# curcut_design.net
KiCad netlist of a schematic drawn in EasyEDA
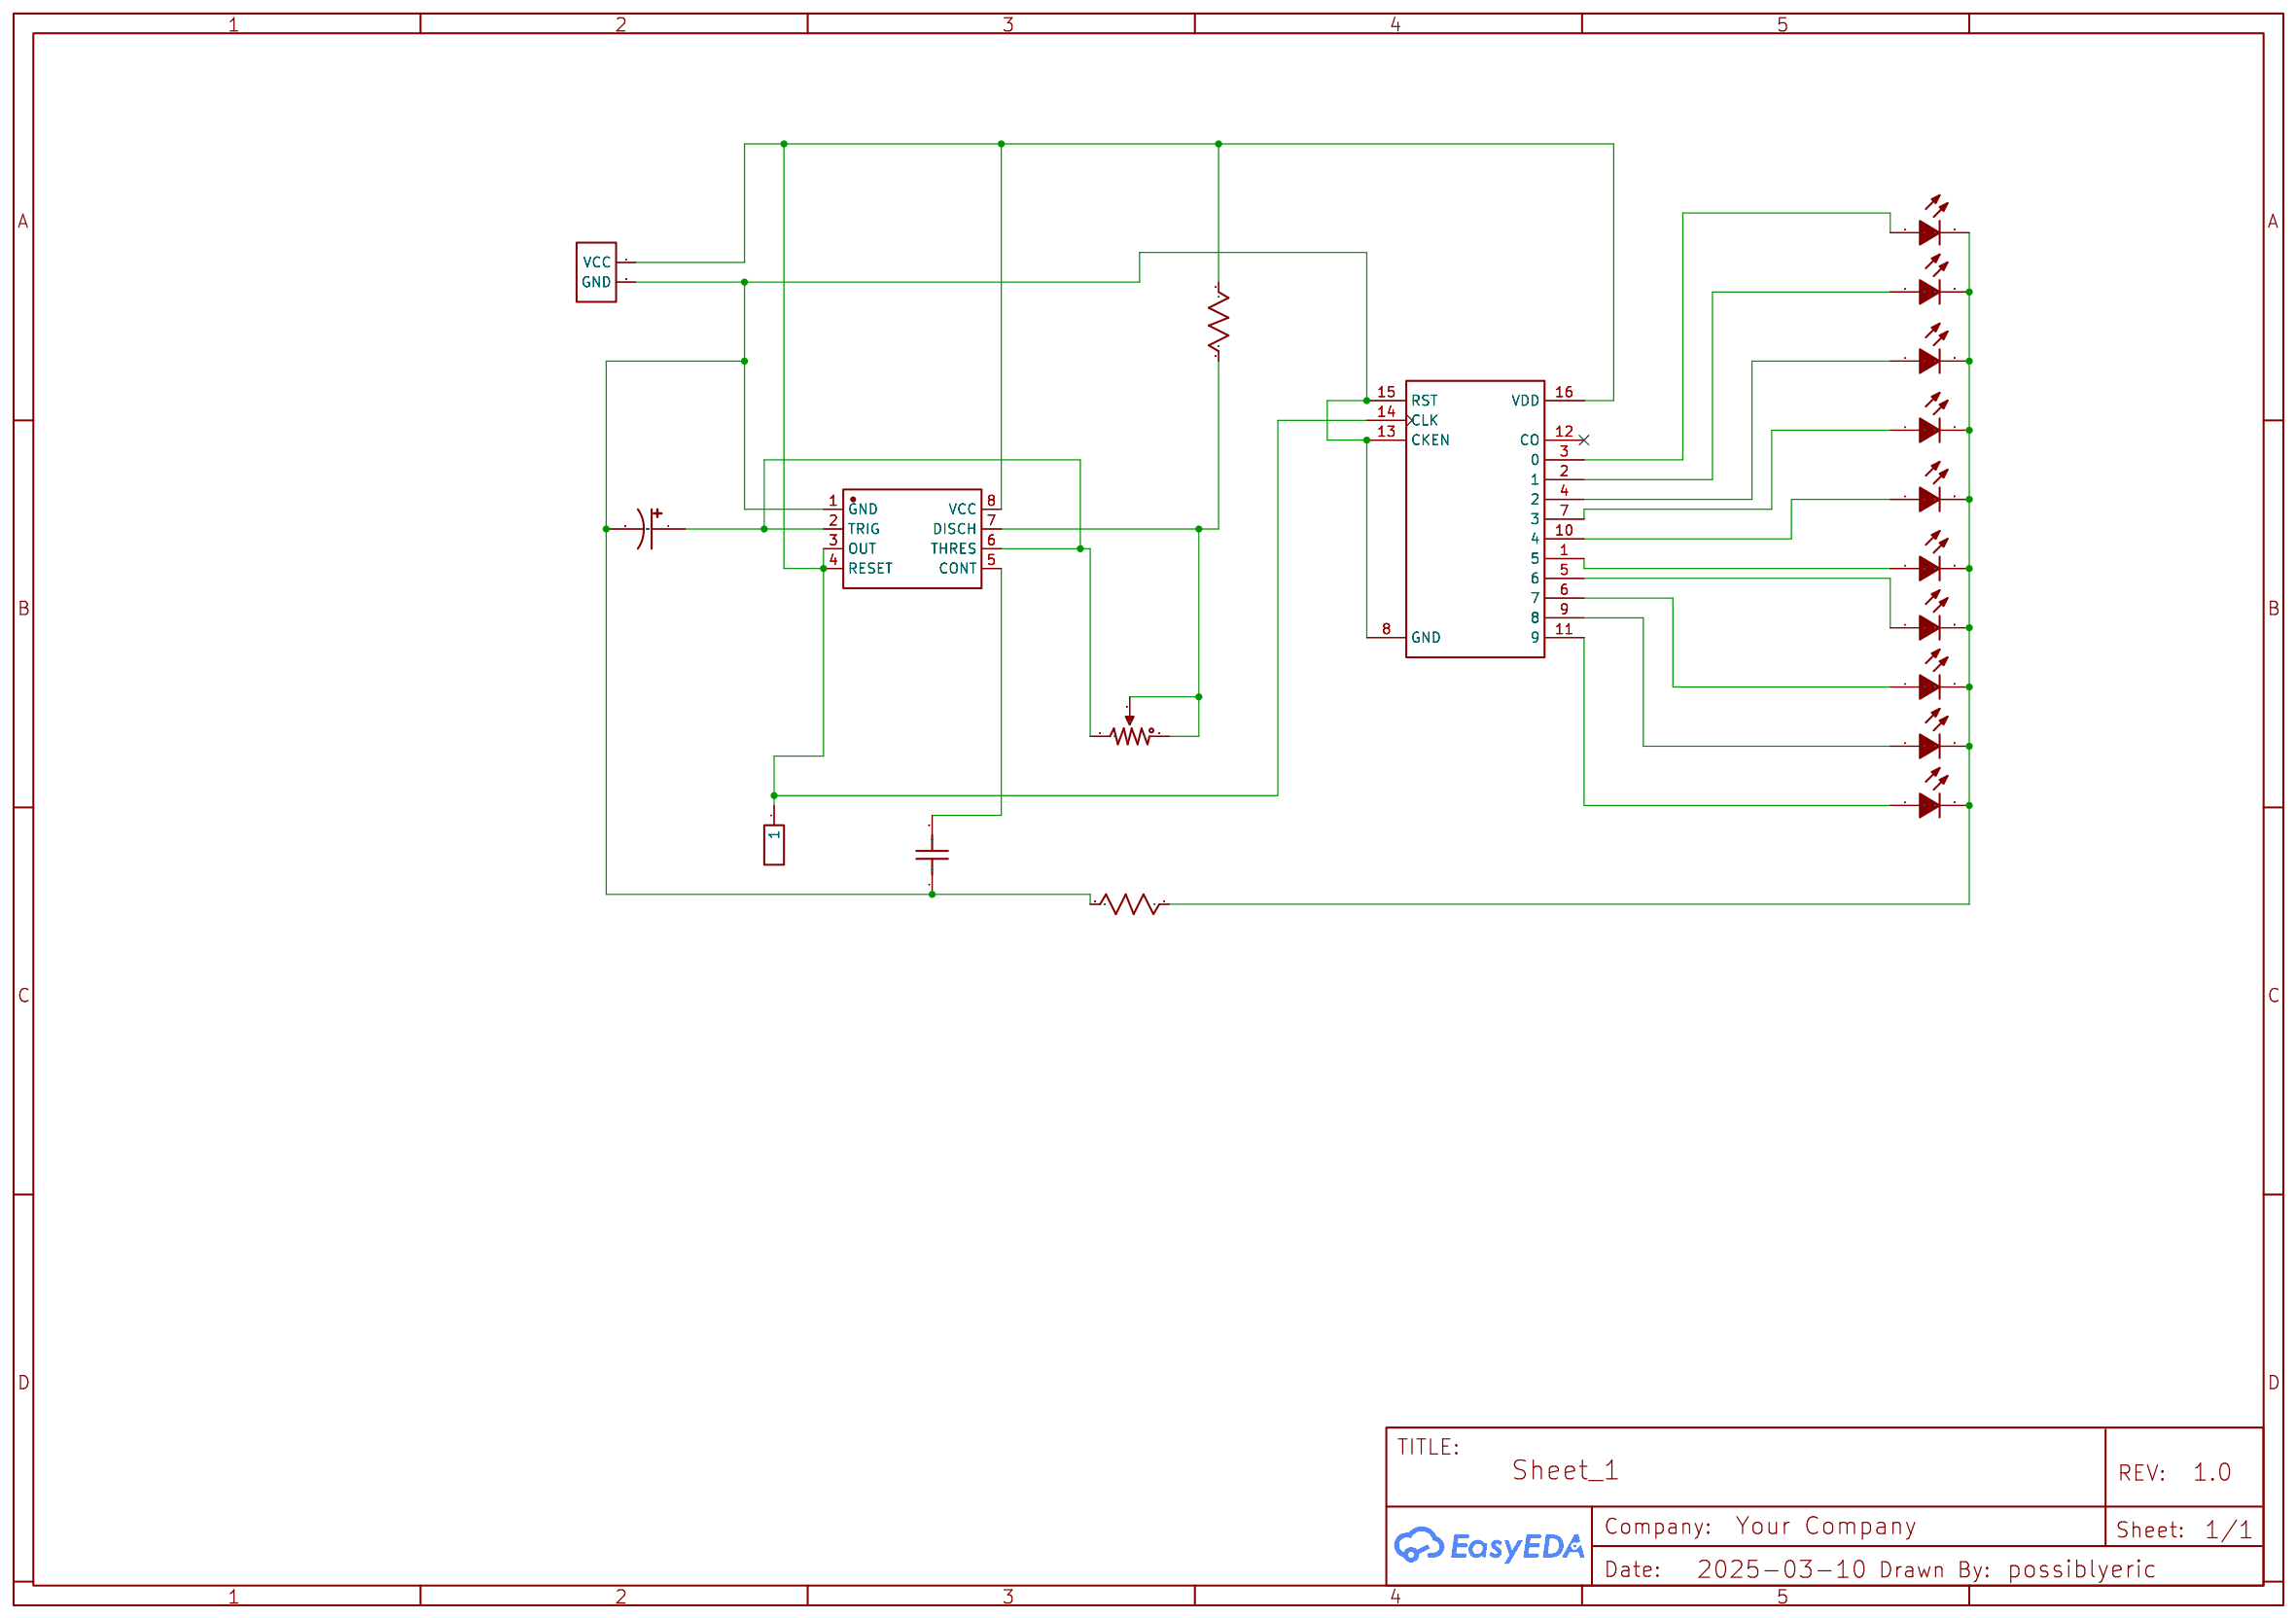
[diagram p0: schematic sheet]

(export (version "E")
  (design (tool "Eeschema 10.0.6"))
  (components
    (comp (ref "1") (value "LED_5MM") (libsource (lib "") (part "LED_5MM")))
    (comp (ref "2") (value "LED_5MM") (libsource (lib "") (part "LED_5MM")))
    (comp (ref "3") (value "LED_5MM") (libsource (lib "") (part "LED_5MM")))
    (comp (ref "4") (value "LED_5MM") (libsource (lib "") (part "LED_5MM")))
    (comp (ref "5") (value "LED_5MM") (libsource (lib "") (part "LED_5MM")))
    (comp (ref "6") (value "LED_5MM") (libsource (lib "") (part "LED_5MM")))
    (comp (ref "7") (value "LED_5MM") (libsource (lib "") (part "LED_5MM")))
    (comp (ref "8") (value "LED_5MM") (libsource (lib "") (part "LED_5MM")))
    (comp (ref "9") (value "LED_5MM") (libsource (lib "") (part "LED_5MM")))
    (comp (ref "10") (value "LED_5MM") (libsource (lib "") (part "LED_5MM")))
    (comp (ref "C1")
      (value "1uF")
      (fields (field (name "Manufacturer Part") "UVZ1H010MDD") (field (name "Manufacturer") "Nichicon(尼吉康)"))
      (libsource (lib "") (part "UVZ1H010MDD"))
    )
    (comp (ref "C2") (value "0.01u") (libsource (lib "") (part "C_0603_US")))
    (comp (ref "CLK1")
      (value "C81276")
      (fields
        (field (name "Manufacturer Part") "2.54-1*1P针")
        (field (name "Manufacturer") "BOOMELE(Boom Precision Elec)")
      )
      (libsource (lib "") (part "Header-Male-2.54_1x1"))
    )
    (comp (ref "H1") (value "Header") (libsource (lib "") (part "HEADER-FEMALE-2.54_1X2")))
    (comp (ref "R1")
      (value "470")
      (fields (field (name "Manufacturer Part") "?"))
      (libsource (lib "") (part "Resistor"))
    )
    (comp (ref "R2")
      (value "1k")
      (fields (field (name "Manufacturer Part") "?"))
      (libsource (lib "") (part "Resistor_1"))
    )
    (comp (ref "R4")
      (value "50k")
      (fields (field (name "Manufacturer Part") "?"))
      (libsource (lib "") (part "Potentiometer"))
    )
    (comp (ref "U2")
      (value "NE555P")
      (fields (field (name "Manufacturer") "TI(德州仪器)"))
      (libsource (lib "") (part "NE555P"))
    )
    (comp (ref "U4") (value "CD4017BCN") (libsource (lib "") (part "CD4017BCN")))
  )
  (nets
    (net (code "1") (name "Net-(1-A)") (class "Default")
      (node (ref "1") (pin "1") (pinfunction "A_1") (pintype "input"))
      (node (ref "U4") (pin "3") (pinfunction "0_3") (pintype "output"))
    )
    (net (code "2") (name "Net-(1-K)") (class "Default")
      (node (ref "1") (pin "2") (pinfunction "K_2") (pintype "input"))
      (node (ref "10") (pin "2") (pinfunction "K_2") (pintype "input"))
      (node (ref "2") (pin "2") (pinfunction "K_2") (pintype "input"))
      (node (ref "3") (pin "2") (pinfunction "K_2") (pintype "input"))
      (node (ref "4") (pin "2") (pinfunction "K_2") (pintype "input"))
      (node (ref "5") (pin "2") (pinfunction "K_2") (pintype "input"))
      (node (ref "6") (pin "2") (pinfunction "K_2") (pintype "input"))
      (node (ref "7") (pin "2") (pinfunction "K_2") (pintype "input"))
      (node (ref "8") (pin "2") (pinfunction "K_2") (pintype "input"))
      (node (ref "9") (pin "2") (pinfunction "K_2") (pintype "input"))
      (node (ref "R1") (pin "1") (pinfunction "1_1") (pintype "unspecified"))
    )
    (net (code "3") (name "Net-(2-A)") (class "Default")
      (node (ref "2") (pin "1") (pinfunction "A_1") (pintype "input"))
      (node (ref "U4") (pin "2") (pinfunction "1_2") (pintype "output"))
    )
    (net (code "4") (name "Net-(3-A)") (class "Default")
      (node (ref "3") (pin "1") (pinfunction "A_1") (pintype "input"))
      (node (ref "U4") (pin "4") (pinfunction "2_4") (pintype "output"))
    )
    (net (code "5") (name "Net-(4-A)") (class "Default")
      (node (ref "4") (pin "1") (pinfunction "A_1") (pintype "input"))
      (node (ref "U4") (pin "7") (pinfunction "3_7") (pintype "output"))
    )
    (net (code "6") (name "Net-(5-A)") (class "Default")
      (node (ref "5") (pin "1") (pinfunction "A_1") (pintype "input"))
      (node (ref "U4") (pin "10") (pinfunction "4_10") (pintype "output"))
    )
    (net (code "7") (name "Net-(6-A)") (class "Default")
      (node (ref "6") (pin "1") (pinfunction "A_1") (pintype "input"))
      (node (ref "U4") (pin "1") (pinfunction "5_1") (pintype "output"))
    )
    (net (code "8") (name "Net-(7-A)") (class "Default")
      (node (ref "7") (pin "1") (pinfunction "A_1") (pintype "input"))
      (node (ref "U4") (pin "5") (pinfunction "6_5") (pintype "output"))
    )
    (net (code "9") (name "Net-(8-A)") (class "Default")
      (node (ref "8") (pin "1") (pinfunction "A_1") (pintype "input"))
      (node (ref "U4") (pin "6") (pinfunction "7_6") (pintype "output"))
    )
    (net (code "10") (name "Net-(9-A)") (class "Default")
      (node (ref "9") (pin "1") (pinfunction "A_1") (pintype "input"))
      (node (ref "U4") (pin "9") (pinfunction "8_9") (pintype "output"))
    )
    (net (code "11") (name "Net-(10-A)") (class "Default")
      (node (ref "10") (pin "1") (pinfunction "A_1") (pintype "input"))
      (node (ref "U4") (pin "11") (pinfunction "9_11") (pintype "output"))
    )
    (net (code "12") (name "Net-(H1-GND)") (class "Default")
      (node (ref "C1") (pin "2") (pinfunction "2_2") (pintype "unspecified"))
      (node (ref "C2") (pin "1") (pinfunction "1_1") (pintype "unspecified"))
      (node (ref "H1") (pin "2") (pinfunction "GND_2") (pintype "unspecified"))
      (node (ref "R1") (pin "2") (pinfunction "2_2") (pintype "unspecified"))
      (node (ref "U2") (pin "1") (pinfunction "GND_1") (pintype "unspecified"))
      (node (ref "U4") (pin "13") (pinfunction "CKEN_13") (pintype "unspecified"))
      (node (ref "U4") (pin "15") (pinfunction "RST_15") (pintype "unspecified"))
      (node (ref "U4") (pin "8") (pinfunction "GND_8") (pintype "passive"))
    )
    (net (code "13") (name "Net-(H1-VCC)") (class "Default")
      (node (ref "CLK1") (pin "1") (pinfunction "1_1") (pintype "unspecified"))
      (node (ref "H1") (pin "1") (pinfunction "VCC_1") (pintype "unspecified"))
      (node (ref "R2") (pin "1") (pinfunction "1_1") (pintype "unspecified"))
      (node (ref "U2") (pin "3") (pinfunction "OUT_3") (pintype "unspecified"))
      (node (ref "U2") (pin "4") (pinfunction "RESET_4") (pintype "unspecified"))
      (node (ref "U2") (pin "8") (pinfunction "VCC_8") (pintype "unspecified"))
      (node (ref "U4") (pin "14") (pinfunction "CLK_14") (pintype "unspecified"))
      (node (ref "U4") (pin "16") (pinfunction "VDD_16") (pintype "passive"))
    )
    (net (code "14") (name "Net-(R4-2)") (class "Default")
      (node (ref "R2") (pin "2") (pinfunction "2_2") (pintype "unspecified"))
      (node (ref "R4") (pin "2") (pinfunction "3_2") (pintype "unspecified"))
      (node (ref "R4") (pin "3") (pinfunction "2_3") (pintype "unspecified"))
      (node (ref "U2") (pin "7") (pinfunction "DISCH_7") (pintype "unspecified"))
    )
    (net (code "15") (name "Net-(U2-CONT)") (class "Default")
      (node (ref "C2") (pin "2") (pinfunction "2_2") (pintype "unspecified"))
      (node (ref "U2") (pin "5") (pinfunction "CONT_5") (pintype "unspecified"))
    )
    (net (code "16") (name "Net-(U2-THRES)") (class "Default")
      (node (ref "C1") (pin "1") (pinfunction "1_1") (pintype "unspecified"))
      (node (ref "R4") (pin "1") (pinfunction "1_1") (pintype "unspecified"))
      (node (ref "U2") (pin "2") (pinfunction "TRIG_2") (pintype "unspecified"))
      (node (ref "U2") (pin "6") (pinfunction "THRES_6") (pintype "unspecified"))
    )
    (net (code "17") (name "unconnected-(U4-CO-Pad12)") (class "Default")
      (node (ref "U4") (pin "12") (pinfunction "CO_12") (pintype "output+no_connect"))
    )
  )
)
